# easyeda_aapen_term.net
KiCad netlist of a schematic drawn in EasyEDA
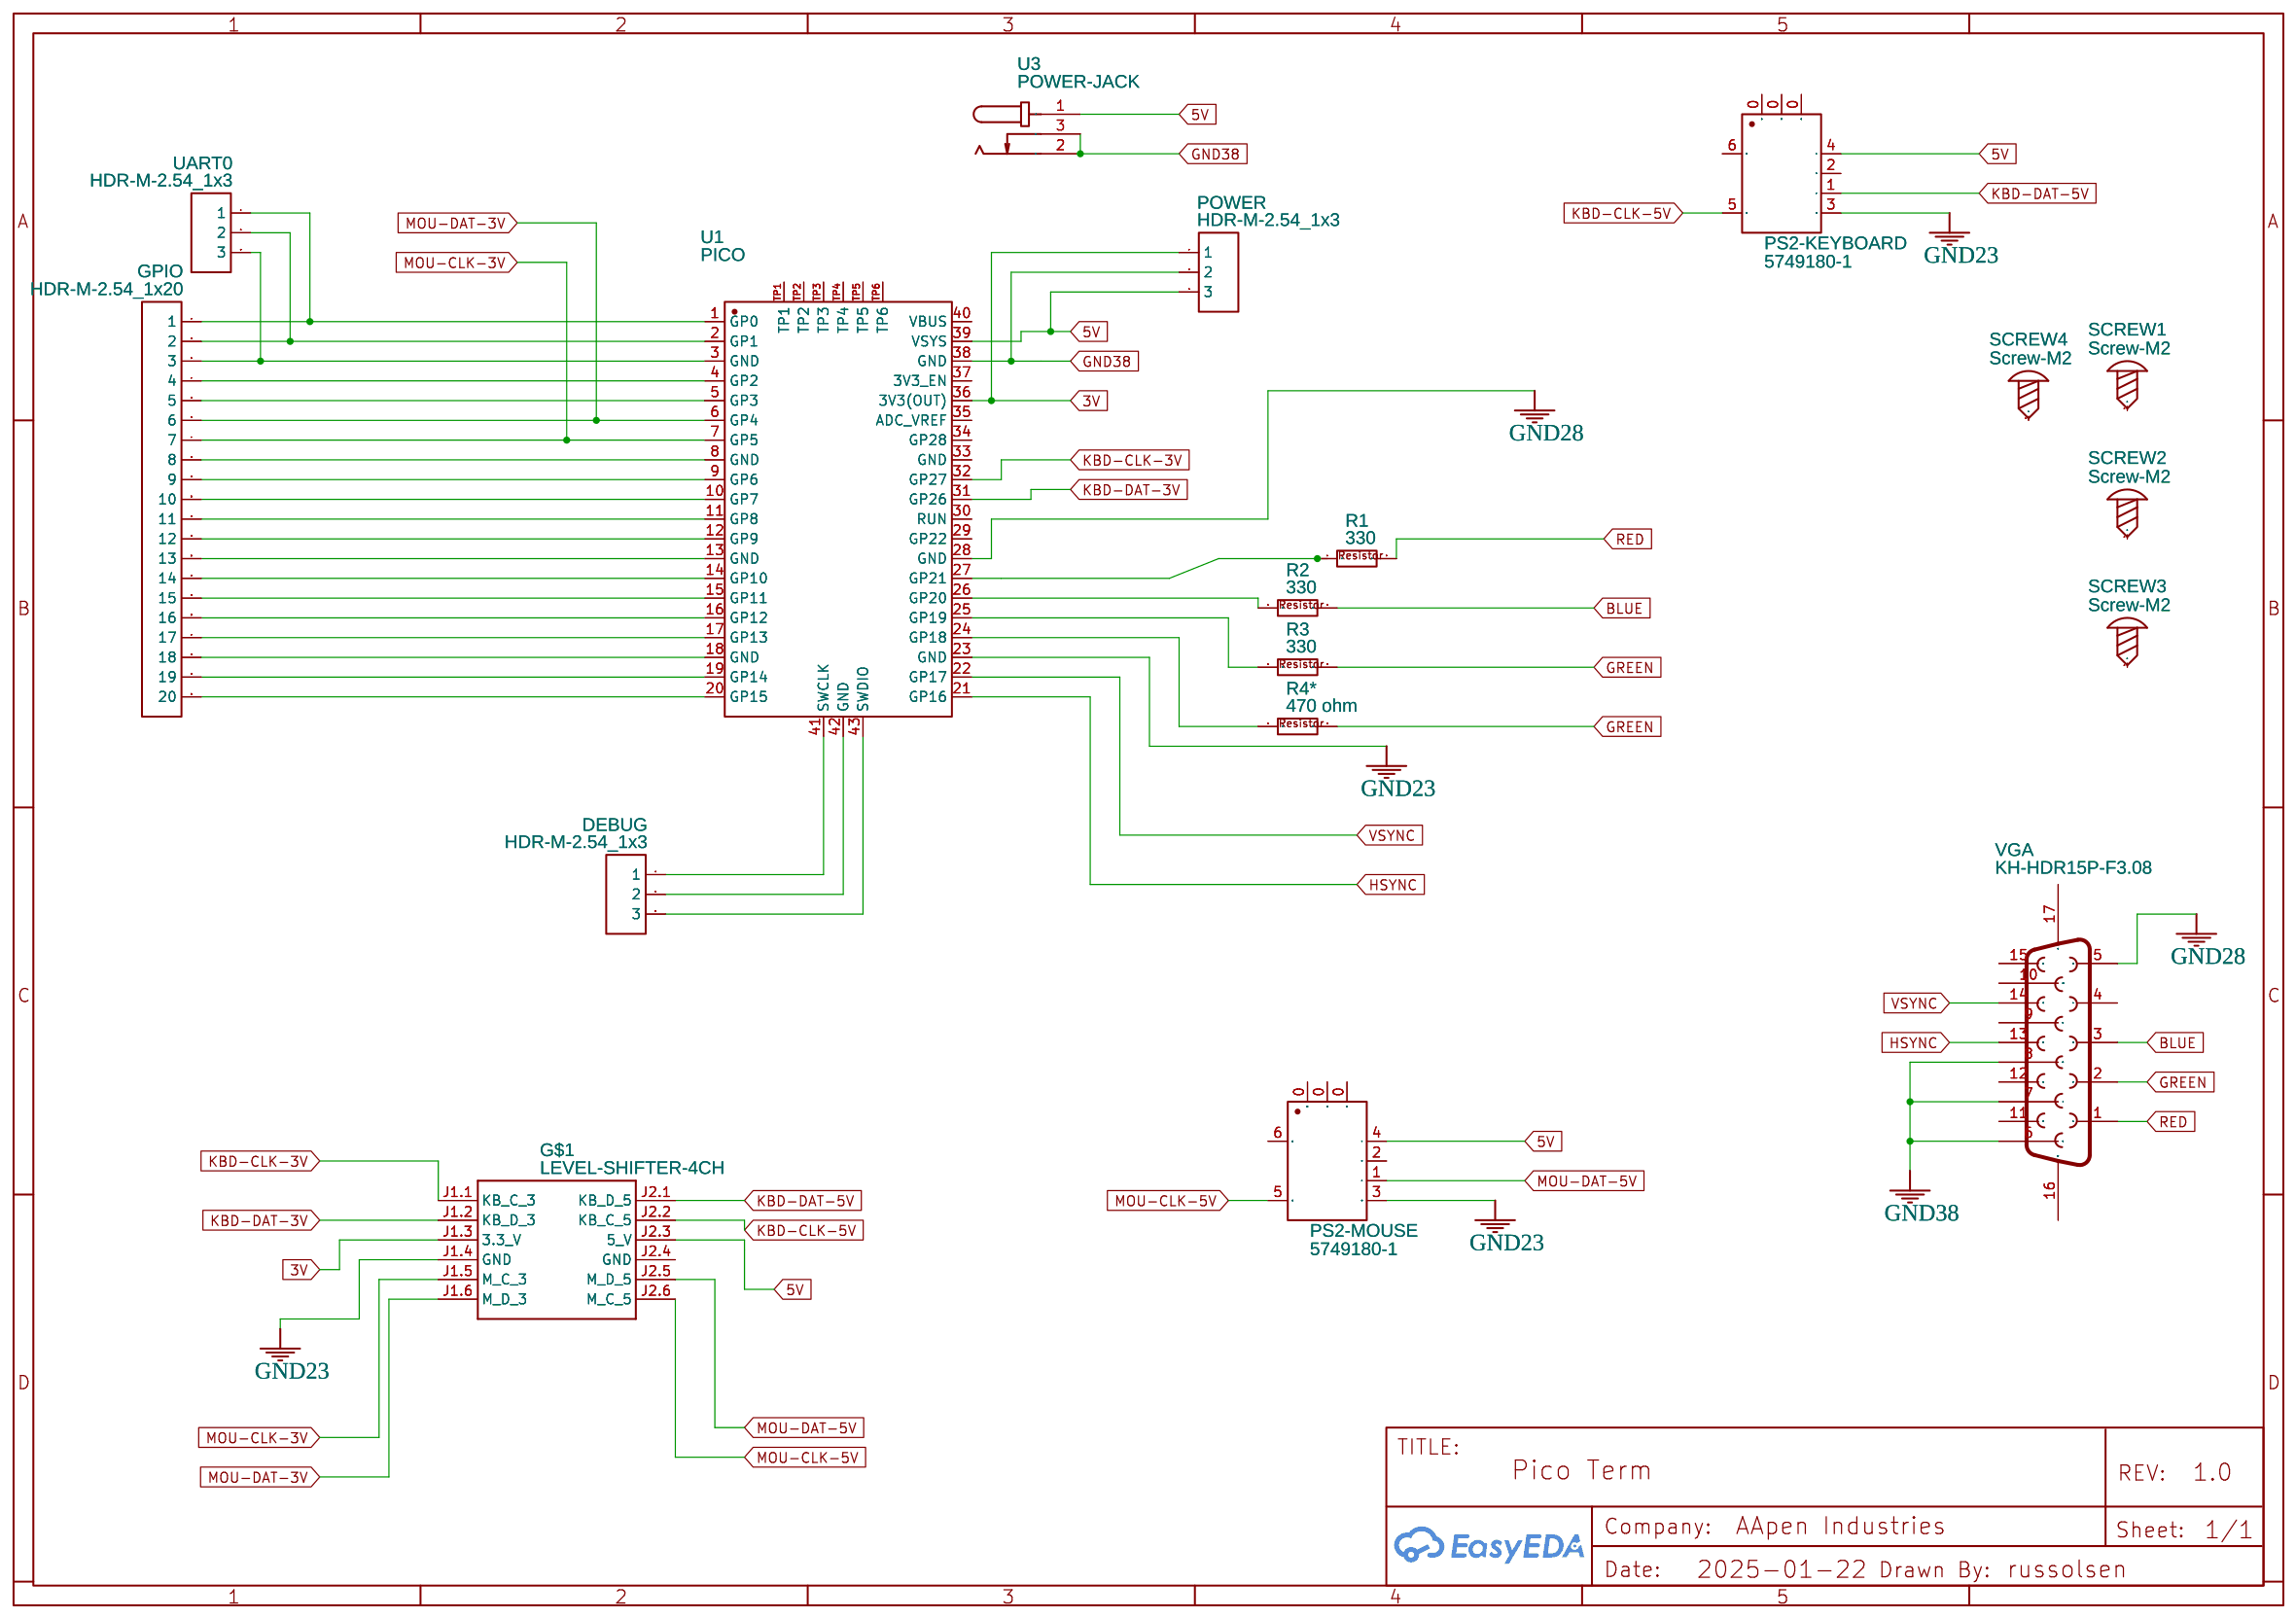
[diagram p0: schematic sheet]

(export (version "E")
  (design (tool "Eeschema 10.0.6"))
  (components
    (comp (ref "DEBUG") (value "HDR-M-2.54_1x3") (libsource (lib "") (part "HDR-M-2.54_1x3")))
    (comp (ref "G$1") (value "LEVEL-SHIFTER-4CH") (libsource (lib "") (part "LEVEL-SHIFTER-4CH")))
    (comp (ref "GPIO") (value "HDR-M-2.54_1x20") (libsource (lib "") (part "HDR-M-2.54_1x20")))
    (comp (ref "POWER") (value "HDR-M-2.54_1x3") (libsource (lib "") (part "HDR-M-2.54_1x3_1")))
    (comp (ref "PS2-KEYBOARD")
      (value "5749180-1")
      (fields (field (name "Manufacturer") "TE Connectivity(泰科电子)"))
      (libsource (lib "") (part "5749180-1_1"))
    )
    (comp (ref "PS2-MOUSE")
      (value "5749180-1")
      (fields (field (name "Manufacturer") "TE Connectivity(泰科电子)"))
      (libsource (lib "") (part "5749180-1"))
    )
    (comp (ref "R1")
      (value "330")
      (fields
        (field (name "Manufacturer Part") "EWWR0001J20R0T9")
        (field (name "Manufacturer") "ResistorToday")
      )
      (libsource (lib "") (part "Resistor"))
    )
    (comp (ref "R2")
      (value "330")
      (fields
        (field (name "Manufacturer Part") "EWWR0001J20R0T9")
        (field (name "Manufacturer") "ResistorToday")
      )
      (libsource (lib "") (part "Resistor"))
    )
    (comp (ref "R3")
      (value "330")
      (fields
        (field (name "Manufacturer Part") "EWWR0001J20R0T9")
        (field (name "Manufacturer") "ResistorToday")
      )
      (libsource (lib "") (part "Resistor"))
    )
    (comp (ref "R4*")
      (value "470 ohm")
      (fields
        (field (name "Manufacturer Part") "EWWR0001J20R0T9")
        (field (name "Manufacturer") "ResistorToday")
      )
      (libsource (lib "") (part "Resistor_1"))
    )
    (comp (ref "SCREW1") (value "Screw-M2") (libsource (lib "") (part "Screw-M2")))
    (comp (ref "SCREW2") (value "Screw-M2") (libsource (lib "") (part "Screw-M2")))
    (comp (ref "SCREW3") (value "Screw-M2") (libsource (lib "") (part "Screw-M2")))
    (comp (ref "SCREW4") (value "Screw-M2") (libsource (lib "") (part "Screw-M2")))
    (comp (ref "U1")
      (value "PICO")
      (fields (field (name "Manufacturer") "Raspberry Pi(树莓派)"))
      (libsource (lib "") (part "PICO"))
    )
    (comp (ref "U3")
      (value "POWER-JACK")
      (fields (field (name "Manufacturer") "索峰"))
      (libsource (lib "") (part "POWER-JACK"))
    )
    (comp (ref "UART0") (value "HDR-M-2.54_1x3") (libsource (lib "") (part "HDR-M-2.54_1x3_2")))
    (comp (ref "VGA")
      (value "KH-HDR15P-F3.08")
      (fields (field (name "Manufacturer") "kinghelm(金航标)"))
      (libsource (lib "") (part "KH-HDR15P-F3.08"))
    )
  )
  (nets
    (net (code "1") (name "3V") (class "Default")
      (node (ref "G$1") (pin "J1.3") (pinfunction "3.3_V_J1.3") (pintype "bidirectional"))
      (node (ref "POWER") (pin "1") (pinfunction "1_1") (pintype "input"))
      (node (ref "U1") (pin "36") (pinfunction "3V3(OUT)_36") (pintype "unspecified"))
    )
    (net (code "2") (name "5V") (class "Default")
      (node (ref "G$1") (pin "J2.3") (pinfunction "5_V_J2.3") (pintype "bidirectional"))
      (node (ref "POWER") (pin "3") (pinfunction "3_3") (pintype "input"))
      (node (ref "PS2-KEYBOARD") (pin "4") (pinfunction "4_4") (pintype "unspecified"))
      (node (ref "PS2-MOUSE") (pin "4") (pinfunction "4_4") (pintype "unspecified"))
      (node (ref "U1") (pin "39") (pinfunction "VSYS_39") (pintype "unspecified"))
      (node (ref "U3") (pin "1") (pinfunction "1_1") (pintype "unspecified"))
    )
    (net (code "3") (name "BLUE") (class "Default")
      (node (ref "R2") (pin "2") (pinfunction "2_2") (pintype "unspecified"))
      (node (ref "VGA") (pin "3") (pinfunction "3_3") (pintype "unspecified"))
    )
    (net (code "4") (name "GND23") (class "Default")
      (node (ref "G$1") (pin "J1.4") (pinfunction "GND_J1.4") (pintype "bidirectional"))
      (node (ref "PS2-KEYBOARD") (pin "3") (pinfunction "3_3") (pintype "unspecified"))
      (node (ref "PS2-MOUSE") (pin "3") (pinfunction "3_3") (pintype "unspecified"))
      (node (ref "U1") (pin "23") (pinfunction "GND_23") (pintype "unspecified"))
    )
    (net (code "5") (name "GND28") (class "Default")
      (node (ref "U1") (pin "28") (pinfunction "GND_28") (pintype "unspecified"))
      (node (ref "VGA") (pin "5") (pinfunction "5_5") (pintype "unspecified"))
    )
    (net (code "6") (name "GND38") (class "Default")
      (node (ref "POWER") (pin "2") (pinfunction "2_2") (pintype "input"))
      (node (ref "U1") (pin "38") (pinfunction "GND_38") (pintype "unspecified"))
      (node (ref "U3") (pin "2") (pinfunction "2_2") (pintype "unspecified"))
      (node (ref "U3") (pin "3") (pinfunction "3_3") (pintype "unspecified"))
      (node (ref "VGA") (pin "6") (pinfunction "6_6") (pintype "unspecified"))
      (node (ref "VGA") (pin "7") (pinfunction "7_7") (pintype "unspecified"))
      (node (ref "VGA") (pin "8") (pinfunction "8_8") (pintype "unspecified"))
    )
    (net (code "7") (name "GREEN") (class "Default")
      (node (ref "R3") (pin "2") (pinfunction "2_2") (pintype "unspecified"))
      (node (ref "R4*") (pin "2") (pinfunction "2_2") (pintype "unspecified"))
      (node (ref "VGA") (pin "2") (pinfunction "2_2") (pintype "unspecified"))
    )
    (net (code "8") (name "HSYNC") (class "Default")
      (node (ref "U1") (pin "21") (pinfunction "GP16_21") (pintype "unspecified"))
      (node (ref "VGA") (pin "13") (pinfunction "13_13") (pintype "unspecified"))
    )
    (net (code "9") (name "KBD-CLK-3V") (class "Default")
      (node (ref "G$1") (pin "J1.1") (pinfunction "KB_C_3_J1.1") (pintype "bidirectional"))
      (node (ref "U1") (pin "32") (pinfunction "GP27_32") (pintype "unspecified"))
    )
    (net (code "10") (name "KBD-CLK-5V") (class "Default")
      (node (ref "G$1") (pin "J2.2") (pinfunction "KB_C_5_J2.2") (pintype "bidirectional"))
      (node (ref "PS2-KEYBOARD") (pin "5") (pinfunction "5_5") (pintype "unspecified"))
    )
    (net (code "11") (name "KBD-DAT-3V") (class "Default")
      (node (ref "G$1") (pin "J1.2") (pinfunction "KB_D_3_J1.2") (pintype "bidirectional"))
      (node (ref "U1") (pin "31") (pinfunction "GP26_31") (pintype "unspecified"))
    )
    (net (code "12") (name "KBD-DAT-5V") (class "Default")
      (node (ref "G$1") (pin "J2.1") (pinfunction "KB_D_5_J2.1") (pintype "bidirectional"))
      (node (ref "PS2-KEYBOARD") (pin "1") (pinfunction "1_1") (pintype "unspecified"))
    )
    (net (code "13") (name "MOU-CLK-3V") (class "Default")
      (node (ref "G$1") (pin "J1.5") (pinfunction "M_C_3_J1.5") (pintype "bidirectional"))
      (node (ref "GPIO") (pin "7") (pinfunction "7_7") (pintype "unspecified"))
      (node (ref "U1") (pin "7") (pinfunction "GP5_7") (pintype "unspecified"))
    )
    (net (code "14") (name "MOU-CLK-5V") (class "Default")
      (node (ref "G$1") (pin "J2.6") (pinfunction "M_C_5_J2.6") (pintype "bidirectional"))
      (node (ref "PS2-MOUSE") (pin "5") (pinfunction "5_5") (pintype "unspecified"))
    )
    (net (code "15") (name "MOU-DAT-3V") (class "Default")
      (node (ref "G$1") (pin "J1.6") (pinfunction "M_D_3_J1.6") (pintype "bidirectional"))
      (node (ref "GPIO") (pin "6") (pinfunction "6_6") (pintype "unspecified"))
      (node (ref "U1") (pin "6") (pinfunction "GP4_6") (pintype "unspecified"))
    )
    (net (code "16") (name "MOU-DAT-5V") (class "Default")
      (node (ref "G$1") (pin "J2.5") (pinfunction "M_D_5_J2.5") (pintype "bidirectional"))
      (node (ref "PS2-MOUSE") (pin "1") (pinfunction "1_1") (pintype "unspecified"))
    )
    (net (code "17") (name "Net-(DEBUG-Pad2)") (class "Default")
      (node (ref "DEBUG") (pin "2") (pinfunction "2_2") (pintype "input"))
      (node (ref "U1") (pin "42") (pinfunction "GND_42") (pintype "unspecified"))
    )
    (net (code "18") (name "Net-(GPIO-Pad3)") (class "Default")
      (node (ref "GPIO") (pin "3") (pinfunction "3_3") (pintype "unspecified"))
      (node (ref "U1") (pin "3") (pinfunction "GND_3") (pintype "unspecified"))
      (node (ref "UART0") (pin "3") (pinfunction "3_3") (pintype "input"))
    )
    (net (code "19") (name "Net-(GPIO-Pad8)") (class "Default")
      (node (ref "GPIO") (pin "8") (pinfunction "8_8") (pintype "unspecified"))
      (node (ref "U1") (pin "8") (pinfunction "GND_8") (pintype "unspecified"))
    )
    (net (code "20") (name "Net-(GPIO-Pad13)") (class "Default")
      (node (ref "GPIO") (pin "13") (pinfunction "13_13") (pintype "unspecified"))
      (node (ref "U1") (pin "13") (pinfunction "GND_13") (pintype "unspecified"))
    )
    (net (code "21") (name "Net-(GPIO-Pad18)") (class "Default")
      (node (ref "GPIO") (pin "18") (pinfunction "18_18") (pintype "unspecified"))
      (node (ref "U1") (pin "18") (pinfunction "GND_18") (pintype "unspecified"))
    )
    (net (code "22") (name "Net-(U1-GP0)") (class "Default")
      (node (ref "GPIO") (pin "1") (pinfunction "1_1") (pintype "unspecified"))
      (node (ref "U1") (pin "1") (pinfunction "GP0_1") (pintype "unspecified"))
      (node (ref "UART0") (pin "1") (pinfunction "1_1") (pintype "input"))
    )
    (net (code "23") (name "Net-(U1-GP1)") (class "Default")
      (node (ref "GPIO") (pin "2") (pinfunction "2_2") (pintype "unspecified"))
      (node (ref "U1") (pin "2") (pinfunction "GP1_2") (pintype "unspecified"))
      (node (ref "UART0") (pin "2") (pinfunction "2_2") (pintype "input"))
    )
    (net (code "24") (name "Net-(U1-GP2)") (class "Default")
      (node (ref "GPIO") (pin "4") (pinfunction "4_4") (pintype "unspecified"))
      (node (ref "U1") (pin "4") (pinfunction "GP2_4") (pintype "unspecified"))
    )
    (net (code "25") (name "Net-(U1-GP3)") (class "Default")
      (node (ref "GPIO") (pin "5") (pinfunction "5_5") (pintype "unspecified"))
      (node (ref "U1") (pin "5") (pinfunction "GP3_5") (pintype "unspecified"))
    )
    (net (code "26") (name "Net-(U1-GP6)") (class "Default")
      (node (ref "GPIO") (pin "9") (pinfunction "9_9") (pintype "unspecified"))
      (node (ref "U1") (pin "9") (pinfunction "GP6_9") (pintype "unspecified"))
    )
    (net (code "27") (name "Net-(U1-GP7)") (class "Default")
      (node (ref "GPIO") (pin "10") (pinfunction "10_10") (pintype "unspecified"))
      (node (ref "U1") (pin "10") (pinfunction "GP7_10") (pintype "unspecified"))
    )
    (net (code "28") (name "Net-(U1-GP8)") (class "Default")
      (node (ref "GPIO") (pin "11") (pinfunction "11_11") (pintype "unspecified"))
      (node (ref "U1") (pin "11") (pinfunction "GP8_11") (pintype "unspecified"))
    )
    (net (code "29") (name "Net-(U1-GP9)") (class "Default")
      (node (ref "GPIO") (pin "12") (pinfunction "12_12") (pintype "unspecified"))
      (node (ref "U1") (pin "12") (pinfunction "GP9_12") (pintype "unspecified"))
    )
    (net (code "30") (name "Net-(U1-GP10)") (class "Default")
      (node (ref "GPIO") (pin "14") (pinfunction "14_14") (pintype "unspecified"))
      (node (ref "U1") (pin "14") (pinfunction "GP10_14") (pintype "unspecified"))
    )
    (net (code "31") (name "Net-(U1-GP11)") (class "Default")
      (node (ref "GPIO") (pin "15") (pinfunction "15_15") (pintype "unspecified"))
      (node (ref "U1") (pin "15") (pinfunction "GP11_15") (pintype "unspecified"))
    )
    (net (code "32") (name "Net-(U1-GP12)") (class "Default")
      (node (ref "GPIO") (pin "16") (pinfunction "16_16") (pintype "unspecified"))
      (node (ref "U1") (pin "16") (pinfunction "GP12_16") (pintype "unspecified"))
    )
    (net (code "33") (name "Net-(U1-GP13)") (class "Default")
      (node (ref "GPIO") (pin "17") (pinfunction "17_17") (pintype "unspecified"))
      (node (ref "U1") (pin "17") (pinfunction "GP13_17") (pintype "unspecified"))
    )
    (net (code "34") (name "Net-(U1-GP14)") (class "Default")
      (node (ref "GPIO") (pin "19") (pinfunction "19_19") (pintype "unspecified"))
      (node (ref "U1") (pin "19") (pinfunction "GP14_19") (pintype "unspecified"))
    )
    (net (code "35") (name "Net-(U1-GP15)") (class "Default")
      (node (ref "GPIO") (pin "20") (pinfunction "20_20") (pintype "unspecified"))
      (node (ref "U1") (pin "20") (pinfunction "GP15_20") (pintype "unspecified"))
    )
    (net (code "36") (name "Net-(U1-GP18)") (class "Default")
      (node (ref "R4*") (pin "1") (pinfunction "1_1") (pintype "unspecified"))
      (node (ref "U1") (pin "24") (pinfunction "GP18_24") (pintype "unspecified"))
    )
    (net (code "37") (name "Net-(U1-GP19)") (class "Default")
      (node (ref "R3") (pin "1") (pinfunction "1_1") (pintype "unspecified"))
      (node (ref "U1") (pin "25") (pinfunction "GP19_25") (pintype "unspecified"))
    )
    (net (code "38") (name "Net-(U1-GP20)") (class "Default")
      (node (ref "R2") (pin "1") (pinfunction "1_1") (pintype "unspecified"))
      (node (ref "U1") (pin "26") (pinfunction "GP20_26") (pintype "unspecified"))
    )
    (net (code "39") (name "Net-(U1-GP21)") (class "Default")
      (node (ref "R1") (pin "1") (pinfunction "1_1") (pintype "unspecified"))
      (node (ref "U1") (pin "27") (pinfunction "GP21_27") (pintype "unspecified"))
    )
    (net (code "40") (name "Net-(U1-SWCLK)") (class "Default")
      (node (ref "DEBUG") (pin "1") (pinfunction "1_1") (pintype "input"))
      (node (ref "U1") (pin "41") (pinfunction "SWCLK_41") (pintype "unspecified"))
    )
    (net (code "41") (name "Net-(U1-SWDIO)") (class "Default")
      (node (ref "DEBUG") (pin "3") (pinfunction "3_3") (pintype "input"))
      (node (ref "U1") (pin "43") (pinfunction "SWDIO_43") (pintype "unspecified"))
    )
    (net (code "42") (name "RED") (class "Default")
      (node (ref "R1") (pin "2") (pinfunction "2_2") (pintype "unspecified"))
      (node (ref "VGA") (pin "1") (pinfunction "1_1") (pintype "unspecified"))
    )
    (net (code "43") (name "VSYNC") (class "Default")
      (node (ref "U1") (pin "22") (pinfunction "GP17_22") (pintype "unspecified"))
      (node (ref "VGA") (pin "14") (pinfunction "14_14") (pintype "unspecified"))
    )
    (net (code "44") (name "unconnected-(G$1-GND-PadJ2.4)") (class "Default")
      (node (ref "G$1") (pin "J2.4") (pinfunction "GND_J2.4") (pintype "bidirectional"))
    )
    (net (code "45") (name "unconnected-(PS2-KEYBOARD-Pad0)") (class "Default")
      (node (ref "PS2-KEYBOARD") (pin "0") (pinfunction "0_0") (pintype "unspecified"))
    )
    (net (code "46") (name "unconnected-(PS2-KEYBOARD-Pad0)_1") (class "Default")
      (node (ref "PS2-KEYBOARD") (pin "0") (pinfunction "0_0") (pintype "unspecified"))
    )
    (net (code "47") (name "unconnected-(PS2-KEYBOARD-Pad0)_2") (class "Default")
      (node (ref "PS2-KEYBOARD") (pin "0") (pinfunction "0_0") (pintype "unspecified"))
    )
    (net (code "48") (name "unconnected-(PS2-KEYBOARD-Pad2)") (class "Default")
      (node (ref "PS2-KEYBOARD") (pin "2") (pinfunction "2_2") (pintype "unspecified"))
    )
    (net (code "49") (name "unconnected-(PS2-KEYBOARD-Pad6)") (class "Default")
      (node (ref "PS2-KEYBOARD") (pin "6") (pinfunction "6_6") (pintype "unspecified"))
    )
    (net (code "50") (name "unconnected-(PS2-MOUSE-Pad0)") (class "Default")
      (node (ref "PS2-MOUSE") (pin "0") (pinfunction "0_0") (pintype "unspecified"))
    )
    (net (code "51") (name "unconnected-(PS2-MOUSE-Pad0)_1") (class "Default")
      (node (ref "PS2-MOUSE") (pin "0") (pinfunction "0_0") (pintype "unspecified"))
    )
    (net (code "52") (name "unconnected-(PS2-MOUSE-Pad0)_2") (class "Default")
      (node (ref "PS2-MOUSE") (pin "0") (pinfunction "0_0") (pintype "unspecified"))
    )
    (net (code "53") (name "unconnected-(PS2-MOUSE-Pad2)") (class "Default")
      (node (ref "PS2-MOUSE") (pin "2") (pinfunction "2_2") (pintype "unspecified"))
    )
    (net (code "54") (name "unconnected-(PS2-MOUSE-Pad6)") (class "Default")
      (node (ref "PS2-MOUSE") (pin "6") (pinfunction "6_6") (pintype "unspecified"))
    )
    (net (code "55") (name "unconnected-(SCREW1-Pad1)") (class "Default")
      (node (ref "SCREW1") (pin "1") (pinfunction "1_1") (pintype "unspecified"))
    )
    (net (code "56") (name "unconnected-(SCREW2-Pad1)") (class "Default")
      (node (ref "SCREW2") (pin "1") (pinfunction "1_1") (pintype "unspecified"))
    )
    (net (code "57") (name "unconnected-(SCREW3-Pad1)") (class "Default")
      (node (ref "SCREW3") (pin "1") (pinfunction "1_1") (pintype "unspecified"))
    )
    (net (code "58") (name "unconnected-(SCREW4-Pad1)") (class "Default")
      (node (ref "SCREW4") (pin "1") (pinfunction "1_1") (pintype "unspecified"))
    )
    (net (code "59") (name "unconnected-(U1-3V3_EN-Pad37)") (class "Default")
      (node (ref "U1") (pin "37") (pinfunction "3V3_EN_37") (pintype "unspecified"))
    )
    (net (code "60") (name "unconnected-(U1-ADC_VREF-Pad35)") (class "Default")
      (node (ref "U1") (pin "35") (pinfunction "ADC_VREF_35") (pintype "unspecified"))
    )
    (net (code "61") (name "unconnected-(U1-GND-Pad33)") (class "Default")
      (node (ref "U1") (pin "33") (pinfunction "GND_33") (pintype "unspecified"))
    )
    (net (code "62") (name "unconnected-(U1-GP22-Pad29)") (class "Default")
      (node (ref "U1") (pin "29") (pinfunction "GP22_29") (pintype "unspecified"))
    )
    (net (code "63") (name "unconnected-(U1-GP28-Pad34)") (class "Default")
      (node (ref "U1") (pin "34") (pinfunction "GP28_34") (pintype "unspecified"))
    )
    (net (code "64") (name "unconnected-(U1-PadTP1)") (class "Default")
      (node (ref "U1") (pin "TP1") (pinfunction "TP1_TP1") (pintype "unspecified"))
    )
    (net (code "65") (name "unconnected-(U1-PadTP2)") (class "Default")
      (node (ref "U1") (pin "TP2") (pinfunction "TP2_TP2") (pintype "unspecified"))
    )
    (net (code "66") (name "unconnected-(U1-PadTP3)") (class "Default")
      (node (ref "U1") (pin "TP3") (pinfunction "TP3_TP3") (pintype "unspecified"))
    )
    (net (code "67") (name "unconnected-(U1-PadTP4)") (class "Default")
      (node (ref "U1") (pin "TP4") (pinfunction "TP4_TP4") (pintype "unspecified"))
    )
    (net (code "68") (name "unconnected-(U1-PadTP5)") (class "Default")
      (node (ref "U1") (pin "TP5") (pinfunction "TP5_TP5") (pintype "unspecified"))
    )
    (net (code "69") (name "unconnected-(U1-PadTP6)") (class "Default")
      (node (ref "U1") (pin "TP6") (pinfunction "TP6_TP6") (pintype "unspecified"))
    )
    (net (code "70") (name "unconnected-(U1-RUN-Pad30)") (class "Default")
      (node (ref "U1") (pin "30") (pinfunction "RUN_30") (pintype "unspecified"))
    )
    (net (code "71") (name "unconnected-(U1-VBUS-Pad40)") (class "Default")
      (node (ref "U1") (pin "40") (pinfunction "VBUS_40") (pintype "unspecified"))
    )
    (net (code "72") (name "unconnected-(VGA-Pad4)") (class "Default")
      (node (ref "VGA") (pin "4") (pinfunction "4_4") (pintype "unspecified"))
    )
    (net (code "73") (name "unconnected-(VGA-Pad9)") (class "Default")
      (node (ref "VGA") (pin "9") (pinfunction "9_9") (pintype "unspecified"))
    )
    (net (code "74") (name "unconnected-(VGA-Pad10)") (class "Default")
      (node (ref "VGA") (pin "10") (pinfunction "10_10") (pintype "unspecified"))
    )
    (net (code "75") (name "unconnected-(VGA-Pad11)") (class "Default")
      (node (ref "VGA") (pin "11") (pinfunction "11_11") (pintype "unspecified"))
    )
    (net (code "76") (name "unconnected-(VGA-Pad12)") (class "Default")
      (node (ref "VGA") (pin "12") (pinfunction "12_12") (pintype "unspecified"))
    )
    (net (code "77") (name "unconnected-(VGA-Pad15)") (class "Default")
      (node (ref "VGA") (pin "15") (pinfunction "15_15") (pintype "unspecified"))
    )
    (net (code "78") (name "unconnected-(VGA-Pad16)") (class "Default")
      (node (ref "VGA") (pin "16") (pinfunction "16_16") (pintype "unspecified"))
    )
    (net (code "79") (name "unconnected-(VGA-Pad17)") (class "Default")
      (node (ref "VGA") (pin "17") (pinfunction "17_17") (pintype "unspecified"))
    )
  )
)
